# BQ24610.net
KiCad netlist of a schematic drawn in Altium Designer
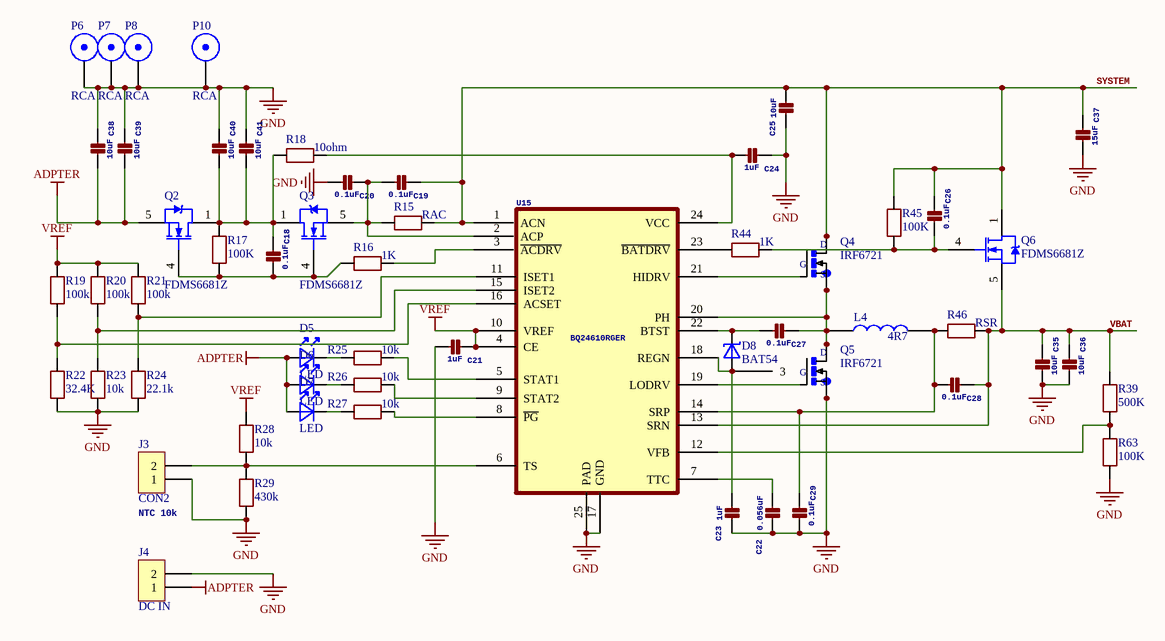
[diagram p0: BQ24610.SchDoc]

(export (version "E")
  (design (tool "Eeschema 10.0.6"))
  (components
    (comp (ref "C18") (value "0.1uF") (footprint "0603AC") (libsource (lib "9G_SCH") (part "CAP")))
    (comp (ref "C19") (value "0.1uF") (footprint "0603AC") (libsource (lib "") (part "CAP_1")))
    (comp (ref "C20") (value "0.1uF") (footprint "0603AC") (libsource (lib "") (part "CAP_1")))
    (comp (ref "C21") (value "1uF") (footprint "0603AC") (libsource (lib "") (part "CAP_1")))
    (comp (ref "C22") (value "0.056uF") (footprint "0603AC") (libsource (lib "") (part "CAP_2")))
    (comp (ref "C23") (value "1uF") (footprint "0603AC") (libsource (lib "") (part "CAP_2")))
    (comp (ref "C24") (value "1uF") (footprint "0603AC") (libsource (lib "") (part "CAP_1")))
    (comp (ref "C25") (value "10uF") (footprint "0603AC") (libsource (lib "") (part "CAP_2")))
    (comp (ref "C26") (value "0.1uF") (footprint "0603AC") (libsource (lib "9G_SCH") (part "CAP")))
    (comp (ref "C27") (value "0.1uF") (footprint "0603AC") (libsource (lib "") (part "CAP_1")))
    (comp (ref "C28") (value "0.1uF") (footprint "0603AC") (libsource (lib "") (part "CAP_1")))
    (comp (ref "C29") (value "0.1uF") (footprint "0603AC") (libsource (lib "9G_SCH") (part "CAP")))
    (comp (ref "C35") (value "10uF") (footprint "1210") (libsource (lib "9G_SCH") (part "CAP")))
    (comp (ref "C36") (value "10uF") (footprint "1210") (libsource (lib "9G_SCH") (part "CAP")))
    (comp (ref "C37") (value "15uF") (footprint "2220") (libsource (lib "9G_SCH") (part "CAP")))
    (comp (ref "C38") (value "10uF") (footprint "1206") (libsource (lib "9G_SCH") (part "CAP")))
    (comp (ref "C39") (value "10uF") (footprint "1206") (libsource (lib "9G_SCH") (part "CAP")))
    (comp (ref "C40") (value "10uF") (footprint "1206") (libsource (lib "9G_SCH") (part "CAP")))
    (comp (ref "C41") (value "10uF") (footprint "1206") (libsource (lib "9G_SCH") (part "CAP")))
    (comp (ref "D5")
      (value "LED")
      (footprint "LED-0805")
      (description "0805 LED")
      (libsource (lib "9G_SCH") (part "LED"))
    )
    (comp (ref "D6")
      (value "LED")
      (footprint "LED-0805")
      (description "0805 LED")
      (libsource (lib "9G_SCH") (part "LED"))
    )
    (comp (ref "D7")
      (value "LED")
      (footprint "LED-0805")
      (description "0805 LED")
      (libsource (lib "9G_SCH") (part "LED"))
    )
    (comp (ref "D8")
      (value "BAT54")
      (footprint "sot-23")
      (libsource (lib "9G_SCH") (part "DIODE SCHOTTKY_1"))
    )
    (comp (ref "J3")
      (value "CON2")
      (footprint "SIP02")
      (description "Therm")
      (libsource (lib "9G_SCH") (part "CON2"))
    )
    (comp (ref "J4")
      (value "DC IN")
      (footprint "DCIN")
      (description "Therm")
      (libsource (lib "9G_SCH") (part "CON2"))
    )
    (comp (ref "L4")
      (value "4R7")
      (footprint "IHLP5050")
      (libsource (lib "Integrated_Library1") (part "INDUCTOR1"))
    )
    (comp (ref "P6")
      (value "RCA")
      (footprint "定位孔 Φ3 1")
      (description "RCA Connector")
      (libsource (lib "插件") (part "RCA"))
    )
    (comp (ref "P7")
      (value "RCA")
      (footprint "定位孔 Φ3 1")
      (description "RCA Connector")
      (libsource (lib "插件") (part "RCA"))
    )
    (comp (ref "P8")
      (value "RCA")
      (footprint "定位孔 Φ3 1")
      (description "RCA Connector")
      (libsource (lib "插件") (part "RCA"))
    )
    (comp (ref "P10")
      (value "RCA")
      (footprint "定位孔 Φ3 1")
      (description "RCA Connector")
      (libsource (lib "插件") (part "RCA"))
    )
    (comp (ref "Q2") (value "FDMS6681Z") (footprint "SON8") (libsource (lib "mosfet") (part "N-Mosfet")))
    (comp (ref "Q3") (value "FDMS6681Z") (footprint "SON8") (libsource (lib "mosfet") (part "N-Mosfet")))
    (comp (ref "Q4")
      (value "IRF6721")
      (footprint "DIRECTFET_IRF6721Primary)")
      (description "Mosfet n-Ch 60v 86a Directfet  -  Irf6648")
      (fields (field (name "MP") "IRF6648") (field (name "MF") "Infineon"))
      (libsource (lib "场效应管及可控硅") (part "IRF6648"))
    )
    (comp (ref "Q5")
      (value "IRF6721")
      (footprint "DIRECTFET_IRF6721Primary)")
      (description "Mosfet n-Ch 60v 86a Directfet  -  Irf6648")
      (fields (field (name "MP") "IRF6648") (field (name "MF") "Infineon"))
      (libsource (lib "场效应管及可控硅") (part "IRF6648"))
    )
    (comp (ref "Q6") (value "FDMS6681Z") (footprint "SON8") (libsource (lib "mosfet") (part "N-Mosfet")))
    (comp (ref "R15")
      (value "RAC")
      (footprint "2010")
      (description "0.01OHM")
      (libsource (lib "9G_SCH") (part "RES2"))
    )
    (comp (ref "R16") (value "1K") (footprint "0603AR") (libsource (lib "9G_SCH") (part "RES2")))
    (comp (ref "R17") (value "100K") (footprint "0603AR") (libsource (lib "9G_SCH") (part "RES2")))
    (comp (ref "R18") (value "10ohm") (footprint "0603AR") (libsource (lib "9G_SCH") (part "RES2")))
    (comp (ref "R19") (value "100k") (footprint "0603AR") (libsource (lib "9G_SCH") (part "RES2")))
    (comp (ref "R20") (value "100k") (footprint "0603AR") (libsource (lib "9G_SCH") (part "RES2")))
    (comp (ref "R21") (value "100k") (footprint "0603AR") (libsource (lib "9G_SCH") (part "RES2")))
    (comp (ref "R22") (value "32.4K") (footprint "0603AR") (libsource (lib "9G_SCH") (part "RES2")))
    (comp (ref "R23") (value "10k") (footprint "0603AR") (libsource (lib "9G_SCH") (part "RES2")))
    (comp (ref "R24") (value "22.1k") (footprint "0603AR") (libsource (lib "9G_SCH") (part "RES2")))
    (comp (ref "R25") (value "10k") (footprint "0603AR") (libsource (lib "9G_SCH") (part "RES2")))
    (comp (ref "R26") (value "10k") (footprint "0603AR") (libsource (lib "9G_SCH") (part "RES2")))
    (comp (ref "R27") (value "10k") (footprint "0603AR") (libsource (lib "9G_SCH") (part "RES2")))
    (comp (ref "R28") (value "10k") (footprint "0603AR") (libsource (lib "9G_SCH") (part "RES2")))
    (comp (ref "R29") (value "430k") (footprint "0603AR") (libsource (lib "9G_SCH") (part "RES2")))
    (comp (ref "R39") (value "500K") (footprint "0603AR") (libsource (lib "9G_SCH") (part "RES2")))
    (comp (ref "R44") (value "1K") (footprint "0603AR") (libsource (lib "9G_SCH") (part "RES2")))
    (comp (ref "R45") (value "100K") (footprint "0603AR") (libsource (lib "9G_SCH") (part "RES2")))
    (comp (ref "R46")
      (value "RSR")
      (footprint "2010")
      (description "0.01OHM")
      (libsource (lib "9G_SCH") (part "RES2"))
    )
    (comp (ref "R63") (value "100K") (footprint "0603AR") (libsource (lib "9G_SCH") (part "RES2")))
    (comp (ref "U15")
      (value "BQ24610RGER")
      (footprint "QFN-24")
      (libsource (lib "9G_SCH") (part "BQ24610RGER"))
    )
  )
  (nets
    (net (code "1") (name "/SYSTEM") (class "Default")
      (node (ref "C19") (pin "1") (pinfunction "1_1") (pintype "passive"))
      (node (ref "C25") (pin "2") (pinfunction "2_2") (pintype "passive"))
      (node (ref "C26") (pin "1") (pinfunction "1_1") (pintype "passive"))
      (node (ref "C37") (pin "1") (pinfunction "1_1") (pintype "passive"))
      (node (ref "Q4") (pin "D") (pinfunction "D_D") (pintype "passive"))
      (node (ref "Q6") (pin "1") (pinfunction "D_1") (pintype "passive"))
      (node (ref "R15") (pin "1") (pinfunction "1_1") (pintype "passive"))
      (node (ref "R45") (pin "1") (pinfunction "1_1") (pintype "passive"))
      (node (ref "U15") (pin "1") (pinfunction "ACN_1") (pintype "passive"))
    )
    (net (code "2") (name "/VBAT") (class "Default")
      (node (ref "C28") (pin "1") (pinfunction "1_1") (pintype "passive"))
      (node (ref "C35") (pin "1") (pinfunction "1_1") (pintype "passive"))
      (node (ref "C36") (pin "1") (pinfunction "1_1") (pintype "passive"))
      (node (ref "Q6") (pin "5") (pinfunction "S_5") (pintype "passive"))
      (node (ref "R39") (pin "1") (pinfunction "1_1") (pintype "passive"))
      (node (ref "R46") (pin "1") (pinfunction "1_1") (pintype "passive"))
      (node (ref "U15") (pin "13") (pinfunction "SRN_13") (pintype "passive"))
    )
    (net (code "3") (name "ADPTER") (class "Default")
      (node (ref "C38") (pin "2") (pinfunction "2_2") (pintype "passive"))
      (node (ref "C39") (pin "2") (pinfunction "2_2") (pintype "passive"))
      (node (ref "D5") (pin "1") (pinfunction "1_1") (pintype "passive"))
      (node (ref "D6") (pin "1") (pinfunction "1_1") (pintype "passive"))
      (node (ref "D7") (pin "1") (pinfunction "1_1") (pintype "passive"))
      (node (ref "J4") (pin "1") (pinfunction "1_1") (pintype "passive"))
      (node (ref "Q2") (pin "5") (pinfunction "S_5") (pintype "passive"))
    )
    (net (code "4") (name "GND") (class "Default")
      (node (ref "C20") (pin "2") (pinfunction "2_2") (pintype "passive"))
      (node (ref "C21") (pin "2") (pinfunction "2_2") (pintype "passive"))
      (node (ref "C22") (pin "1") (pinfunction "1_1") (pintype "passive"))
      (node (ref "C23") (pin "1") (pinfunction "1_1") (pintype "passive"))
      (node (ref "C24") (pin "1") (pinfunction "1_1") (pintype "passive"))
      (node (ref "C25") (pin "1") (pinfunction "1_1") (pintype "passive"))
      (node (ref "C29") (pin "2") (pinfunction "2_2") (pintype "passive"))
      (node (ref "C35") (pin "2") (pinfunction "2_2") (pintype "passive"))
      (node (ref "C36") (pin "2") (pinfunction "2_2") (pintype "passive"))
      (node (ref "C37") (pin "2") (pinfunction "2_2") (pintype "passive"))
      (node (ref "C38") (pin "1") (pinfunction "1_1") (pintype "passive"))
      (node (ref "C39") (pin "1") (pinfunction "1_1") (pintype "passive"))
      (node (ref "C40") (pin "1") (pinfunction "1_1") (pintype "passive"))
      (node (ref "C41") (pin "1") (pinfunction "1_1") (pintype "passive"))
      (node (ref "J3") (pin "1") (pinfunction "1_1") (pintype "passive"))
      (node (ref "J4") (pin "2") (pinfunction "2_2") (pintype "passive"))
      (node (ref "P10") (pin "1") (pinfunction "X_1") (pintype "passive"))
      (node (ref "P6") (pin "1") (pinfunction "X_1") (pintype "passive"))
      (node (ref "P7") (pin "1") (pinfunction "X_1") (pintype "passive"))
      (node (ref "P8") (pin "1") (pinfunction "X_1") (pintype "passive"))
      (node (ref "Q5") (pin "S") (pinfunction "S_S") (pintype "passive"))
      (node (ref "R22") (pin "2") (pinfunction "2_2") (pintype "passive"))
      (node (ref "R23") (pin "2") (pinfunction "2_2") (pintype "passive"))
      (node (ref "R24") (pin "2") (pinfunction "2_2") (pintype "passive"))
      (node (ref "R29") (pin "1") (pinfunction "1_1") (pintype "passive"))
      (node (ref "R63") (pin "2") (pinfunction "2_2") (pintype "passive"))
      (node (ref "U15") (pin "17") (pinfunction "GND_17") (pintype "passive"))
      (node (ref "U15") (pin "25") (pinfunction "PAD_25") (pintype "passive"))
    )
    (net (code "5") (name "Net-(D5-Pad2)") (class "Default")
      (node (ref "D5") (pin "2") (pinfunction "2_2") (pintype "passive"))
      (node (ref "R25") (pin "1") (pinfunction "1_1") (pintype "passive"))
    )
    (net (code "6") (name "Net-(D6-Pad2)") (class "Default")
      (node (ref "D6") (pin "2") (pinfunction "2_2") (pintype "passive"))
      (node (ref "R26") (pin "1") (pinfunction "1_1") (pintype "passive"))
    )
    (net (code "7") (name "Net-(D7-Pad2)") (class "Default")
      (node (ref "D7") (pin "2") (pinfunction "2_2") (pintype "passive"))
      (node (ref "R27") (pin "1") (pinfunction "1_1") (pintype "passive"))
    )
    (net (code "8") (name "Net-(D8-2)") (class "Default")
      (node (ref "C27") (pin "2") (pinfunction "2_2") (pintype "passive"))
      (node (ref "D8") (pin "3") (pinfunction "2_3") (pintype "passive"))
      (node (ref "U15") (pin "22") (pinfunction "BTST_22") (pintype "passive"))
    )
    (net (code "9") (name "Net-(D8-3)") (class "Default")
      (node (ref "C23") (pin "2") (pinfunction "2_2") (pintype "passive"))
      (node (ref "D8") (pin "1") (pinfunction "1_1") (pintype "passive"))
      (node (ref "D8") (pin "2") (pinfunction "3_2") (pintype "passive"))
      (node (ref "U15") (pin "18") (pinfunction "REGN_18") (pintype "passive"))
    )
    (net (code "10") (name "Net-(Q2-D)") (class "Default")
      (node (ref "C18") (pin "1") (pinfunction "1_1") (pintype "passive"))
      (node (ref "C40") (pin "2") (pinfunction "2_2") (pintype "passive"))
      (node (ref "C41") (pin "2") (pinfunction "2_2") (pintype "passive"))
      (node (ref "Q2") (pin "1") (pinfunction "D_1") (pintype "passive"))
      (node (ref "Q3") (pin "1") (pinfunction "D_1") (pintype "passive"))
      (node (ref "R17") (pin "1") (pinfunction "1_1") (pintype "passive"))
      (node (ref "R18") (pin "2") (pinfunction "2_2") (pintype "passive"))
    )
    (net (code "11") (name "Net-(Q2-G)") (class "Default")
      (node (ref "C18") (pin "2") (pinfunction "2_2") (pintype "passive"))
      (node (ref "Q2") (pin "4") (pinfunction "G_4") (pintype "passive"))
      (node (ref "Q3") (pin "4") (pinfunction "G_4") (pintype "passive"))
      (node (ref "R16") (pin "2") (pinfunction "2_2") (pintype "passive"))
      (node (ref "R17") (pin "2") (pinfunction "2_2") (pintype "passive"))
    )
    (net (code "12") (name "Net-(Q3-S)") (class "Default")
      (node (ref "C19") (pin "2") (pinfunction "2_2") (pintype "passive"))
      (node (ref "C20") (pin "1") (pinfunction "1_1") (pintype "passive"))
      (node (ref "Q3") (pin "5") (pinfunction "S_5") (pintype "passive"))
      (node (ref "R15") (pin "2") (pinfunction "2_2") (pintype "passive"))
      (node (ref "U15") (pin "2") (pinfunction "ACP_2") (pintype "passive"))
    )
    (net (code "13") (name "Net-(Q6-G)") (class "Default")
      (node (ref "C26") (pin "2") (pinfunction "2_2") (pintype "passive"))
      (node (ref "Q6") (pin "4") (pinfunction "G_4") (pintype "passive"))
      (node (ref "R44") (pin "1") (pinfunction "1_1") (pintype "passive"))
      (node (ref "R45") (pin "2") (pinfunction "2_2") (pintype "passive"))
    )
    (net (code "14") (name "Net-(U15-ACSET)") (class "Default")
      (node (ref "R19") (pin "2") (pinfunction "2_2") (pintype "passive"))
      (node (ref "R22") (pin "1") (pinfunction "1_1") (pintype "passive"))
      (node (ref "U15") (pin "16") (pinfunction "ACSET_16") (pintype "passive"))
    )
    (net (code "15") (name "Net-(U15-HIDRV)") (class "Default")
      (node (ref "Q4") (pin "G") (pinfunction "G_G") (pintype "passive"))
      (node (ref "U15") (pin "21") (pinfunction "HIDRV_21") (pintype "passive"))
    )
    (net (code "16") (name "Net-(U15-ISET1)") (class "Default")
      (node (ref "R21") (pin "2") (pinfunction "2_2") (pintype "passive"))
      (node (ref "R24") (pin "1") (pinfunction "1_1") (pintype "passive"))
      (node (ref "U15") (pin "11") (pinfunction "ISET1_11") (pintype "passive"))
    )
    (net (code "17") (name "Net-(U15-ISET2)") (class "Default")
      (node (ref "R20") (pin "2") (pinfunction "2_2") (pintype "passive"))
      (node (ref "R23") (pin "1") (pinfunction "1_1") (pintype "passive"))
      (node (ref "U15") (pin "15") (pinfunction "ISET2_15") (pintype "passive"))
    )
    (net (code "18") (name "Net-(U15-LODRV)") (class "Default")
      (node (ref "Q5") (pin "G") (pinfunction "G_G") (pintype "passive"))
      (node (ref "U15") (pin "19") (pinfunction "LODRV_19") (pintype "passive"))
    )
    (net (code "19") (name "Net-(U15-PH)") (class "Default")
      (node (ref "C27") (pin "1") (pinfunction "1_1") (pintype "passive"))
      (node (ref "L4") (pin "1") (pinfunction "1_1") (pintype "passive"))
      (node (ref "Q4") (pin "S") (pinfunction "S_S") (pintype "passive"))
      (node (ref "Q5") (pin "D") (pinfunction "D_D") (pintype "passive"))
      (node (ref "U15") (pin "20") (pinfunction "PH_20") (pintype "passive"))
    )
    (net (code "20") (name "Net-(U15-SRP)") (class "Default")
      (node (ref "C28") (pin "2") (pinfunction "2_2") (pintype "passive"))
      (node (ref "C29") (pin "1") (pinfunction "1_1") (pintype "passive"))
      (node (ref "L4") (pin "2") (pinfunction "2_2") (pintype "passive"))
      (node (ref "R46") (pin "2") (pinfunction "2_2") (pintype "passive"))
      (node (ref "U15") (pin "14") (pinfunction "SRP_14") (pintype "passive"))
    )
    (net (code "21") (name "Net-(U15-STAT1)") (class "Default")
      (node (ref "R25") (pin "2") (pinfunction "2_2") (pintype "passive"))
      (node (ref "U15") (pin "5") (pinfunction "STAT1_5") (pintype "passive"))
    )
    (net (code "22") (name "Net-(U15-STAT2)") (class "Default")
      (node (ref "R26") (pin "2") (pinfunction "2_2") (pintype "passive"))
      (node (ref "U15") (pin "9") (pinfunction "STAT2_9") (pintype "passive"))
    )
    (net (code "23") (name "Net-(U15-TS)") (class "Default")
      (node (ref "J3") (pin "2") (pinfunction "2_2") (pintype "passive"))
      (node (ref "R28") (pin "1") (pinfunction "1_1") (pintype "passive"))
      (node (ref "R29") (pin "2") (pinfunction "2_2") (pintype "passive"))
      (node (ref "U15") (pin "6") (pinfunction "TS_6") (pintype "passive"))
    )
    (net (code "24") (name "Net-(U15-TTC)") (class "Default")
      (node (ref "C22") (pin "2") (pinfunction "2_2") (pintype "passive"))
      (node (ref "U15") (pin "7") (pinfunction "TTC_7") (pintype "passive"))
    )
    (net (code "25") (name "Net-(U15-VCC)") (class "Default")
      (node (ref "C24") (pin "2") (pinfunction "2_2") (pintype "passive"))
      (node (ref "R18") (pin "1") (pinfunction "1_1") (pintype "passive"))
      (node (ref "U15") (pin "24") (pinfunction "VCC_24") (pintype "passive"))
    )
    (net (code "26") (name "Net-(U15-VFB)") (class "Default")
      (node (ref "R39") (pin "2") (pinfunction "2_2") (pintype "passive"))
      (node (ref "R63") (pin "1") (pinfunction "1_1") (pintype "passive"))
      (node (ref "U15") (pin "12") (pinfunction "VFB_12") (pintype "passive"))
    )
    (net (code "27") (name "Net-(U15-~{ACDRV})") (class "Default")
      (node (ref "R16") (pin "1") (pinfunction "1_1") (pintype "passive"))
      (node (ref "U15") (pin "3") (pinfunction "~{ACDRV}_3") (pintype "passive"))
    )
    (net (code "28") (name "Net-(U15-~{BATDRV})") (class "Default")
      (node (ref "R44") (pin "2") (pinfunction "2_2") (pintype "passive"))
      (node (ref "U15") (pin "23") (pinfunction "~{BATDRV}_23") (pintype "passive"))
    )
    (net (code "29") (name "Net-(U15-~{PG})") (class "Default")
      (node (ref "R27") (pin "2") (pinfunction "2_2") (pintype "passive"))
      (node (ref "U15") (pin "8") (pinfunction "~{PG}_8") (pintype "passive"))
    )
    (net (code "30") (name "VREF") (class "Default")
      (node (ref "C21") (pin "1") (pinfunction "1_1") (pintype "passive"))
      (node (ref "R19") (pin "1") (pinfunction "1_1") (pintype "passive"))
      (node (ref "R20") (pin "1") (pinfunction "1_1") (pintype "passive"))
      (node (ref "R21") (pin "1") (pinfunction "1_1") (pintype "passive"))
      (node (ref "R28") (pin "2") (pinfunction "2_2") (pintype "passive"))
      (node (ref "U15") (pin "10") (pinfunction "VREF_10") (pintype "passive"))
      (node (ref "U15") (pin "4") (pinfunction "CE_4") (pintype "passive"))
    )
  )
)
